# imsensor-esp-v01.net
KiCad netlist of a schematic drawn in EAGLE
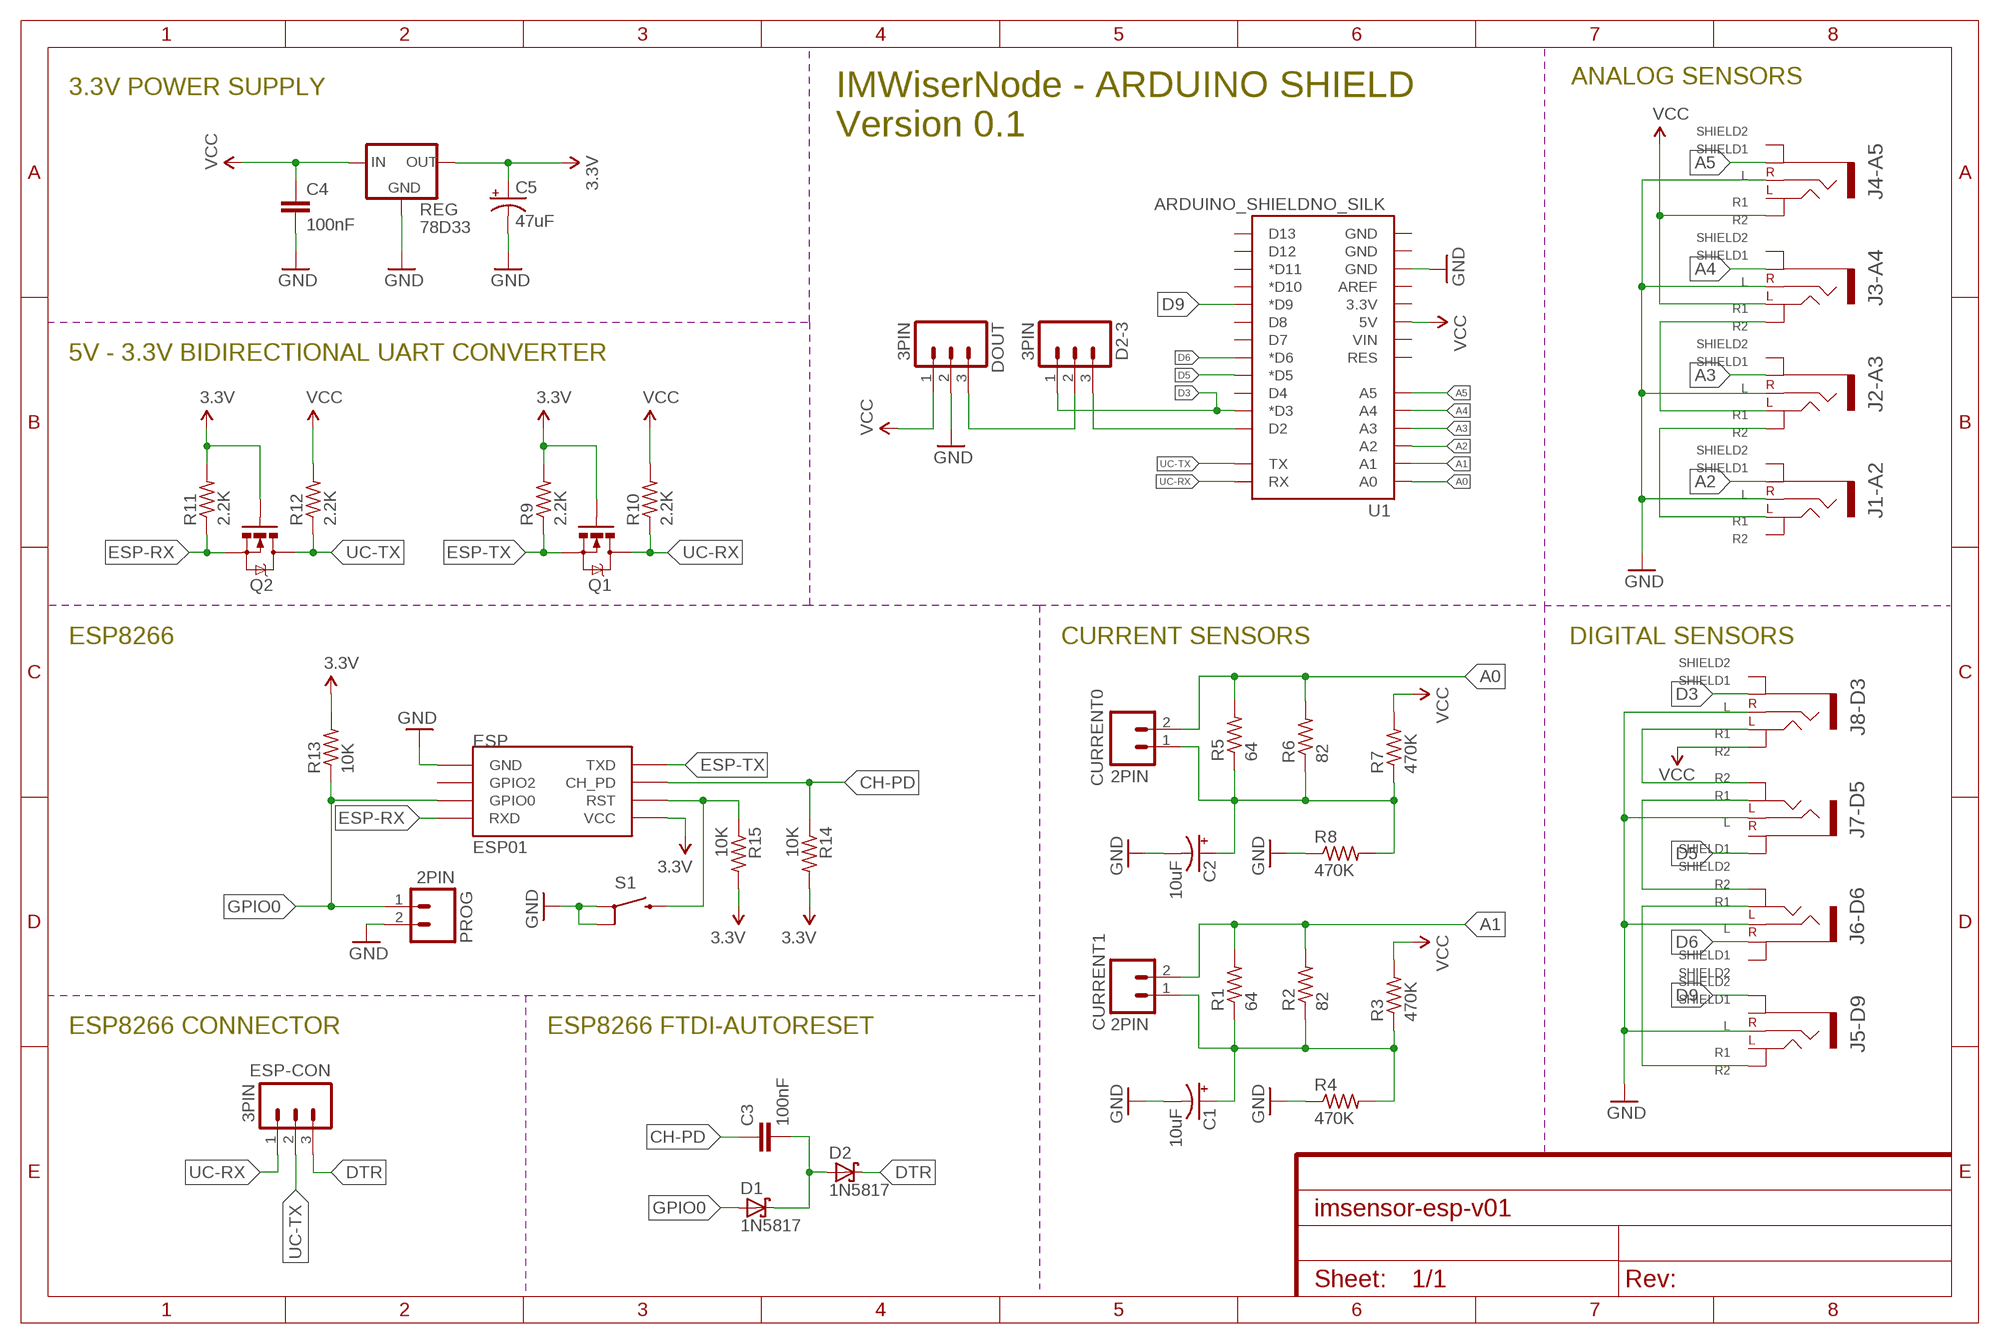
[diagram p0: schematic, sheet 1]

(export (version "E")
  (design (tool "Eeschema 10.0.6"))
  (components
    (comp (ref "C1")
      (value "10uF")
      (footprint "eagle-import:CPOL-RADIAL-10UF-25V")
      (libsource (lib "eagle-import") (part "10UF-25V-20%(PTH)"))
    )
    (comp (ref "C2")
      (value "10uF")
      (footprint "eagle-import:CPOL-RADIAL-10UF-25V")
      (libsource (lib "eagle-import") (part "10UF-25V-20%(PTH)"))
    )
    (comp (ref "C3")
      (value "100nF")
      (footprint "eagle-import:CAP-PTH-SMALL")
      (libsource (lib "eagle-import") (part "CAPPTH"))
    )
    (comp (ref "C4")
      (value "100nF")
      (footprint "eagle-import:CAP-PTH-SMALL")
      (libsource (lib "eagle-import") (part "CAPPTH"))
    )
    (comp (ref "C5")
      (value "47uF")
      (footprint "eagle-import:CPOL-RADIAL-10UF-25V")
      (libsource (lib "eagle-import") (part "10UF-25V-20%(PTH)"))
    )
    (comp (ref "CURRENT0")
      (value "2PIN")
      (footprint "eagle-import:1X02")
      (libsource (lib "eagle-import") (part "M02PTH"))
    )
    (comp (ref "CURRENT1")
      (value "2PIN")
      (footprint "eagle-import:1X02")
      (libsource (lib "eagle-import") (part "M02PTH"))
    )
    (comp (ref "D1")
      (value "1N5817")
      (footprint "eagle-import:DO41-7")
      (libsource (lib "eagle-import") (part "SCHOTTKY-DIODEDO41-7"))
    )
    (comp (ref "D2")
      (value "1N5817")
      (footprint "eagle-import:DO41-7")
      (libsource (lib "eagle-import") (part "SCHOTTKY-DIODEDO41-7"))
    )
    (comp (ref "D2-3")
      (value "3PIN")
      (footprint "eagle-import:1X03")
      (libsource (lib "eagle-import") (part "M03PTH"))
    )
    (comp (ref "DOUT")
      (value "3PIN")
      (footprint "eagle-import:1X03")
      (libsource (lib "eagle-import") (part "M03PTH"))
    )
    (comp (ref "ESP")
      (value "ESP01")
      (footprint "eagle-import:ESP01")
      (libsource (lib "eagle-import") (part "ESP01"))
    )
    (comp (ref "ESP-CON")
      (value "3PIN")
      (footprint "eagle-import:1X03")
      (libsource (lib "eagle-import") (part "M03PTH"))
    )
    (comp (ref "J1-A2")
      (value "PJ-313-SPAD")
      (footprint "eagle-import:PJ-313-5PIN-SMALL")
      (libsource (lib "eagle-import") (part "PJ-313-SPAD"))
    )
    (comp (ref "J2-A3")
      (value "PJ-313-SPAD")
      (footprint "eagle-import:PJ-313-5PIN-SMALL")
      (libsource (lib "eagle-import") (part "PJ-313-SPAD"))
    )
    (comp (ref "J3-A4")
      (value "PJ-313-SPAD")
      (footprint "eagle-import:PJ-313-5PIN-SMALL")
      (libsource (lib "eagle-import") (part "PJ-313-SPAD"))
    )
    (comp (ref "J4-A5")
      (value "PJ-313-SPAD")
      (footprint "eagle-import:PJ-313-5PIN-SMALL")
      (libsource (lib "eagle-import") (part "PJ-313-SPAD"))
    )
    (comp (ref "J5-D9")
      (value "PJ-313-SPAD")
      (footprint "eagle-import:PJ-313-5PIN-SMALL")
      (libsource (lib "eagle-import") (part "PJ-313-SPAD"))
    )
    (comp (ref "J6-D6")
      (value "PJ-313-SPAD")
      (footprint "eagle-import:PJ-313-5PIN-SMALL")
      (libsource (lib "eagle-import") (part "PJ-313-SPAD"))
    )
    (comp (ref "J7-D5")
      (value "PJ-313-SPAD")
      (footprint "eagle-import:PJ-313-5PIN-SMALL")
      (libsource (lib "eagle-import") (part "PJ-313-SPAD"))
    )
    (comp (ref "J8-D3")
      (value "PJ-313-SPAD")
      (footprint "eagle-import:PJ-313-5PIN-SMALL")
      (libsource (lib "eagle-import") (part "PJ-313-SPAD"))
    )
    (comp (ref "PROG")
      (value "2PIN")
      (footprint "eagle-import:1X02")
      (libsource (lib "eagle-import") (part "M02PTH"))
    )
    (comp (ref "Q1")
      (value "MOSFET-NCHANNEL2N7000")
      (footprint "eagle-import:TO-92")
      (libsource (lib "eagle-import") (part "MOSFET-NCHANNEL2N7000"))
    )
    (comp (ref "Q2")
      (value "MOSFET-NCHANNEL2N7000")
      (footprint "eagle-import:TO-92")
      (libsource (lib "eagle-import") (part "MOSFET-NCHANNEL2N7000"))
    )
    (comp (ref "R1")
      (value "64")
      (footprint "eagle-import:0207_10")
      (libsource (lib "eagle-import") (part "R-US_0207/10"))
    )
    (comp (ref "R2")
      (value "82")
      (footprint "eagle-import:0207_10")
      (libsource (lib "eagle-import") (part "R-US_0207/10"))
    )
    (comp (ref "R3")
      (value "470K")
      (footprint "eagle-import:0207_10")
      (libsource (lib "eagle-import") (part "R-US_0207/10"))
    )
    (comp (ref "R4")
      (value "470K")
      (footprint "eagle-import:0207_10")
      (libsource (lib "eagle-import") (part "R-US_0207/10"))
    )
    (comp (ref "R5")
      (value "64")
      (footprint "eagle-import:0207_10")
      (libsource (lib "eagle-import") (part "R-US_0207/10"))
    )
    (comp (ref "R6")
      (value "82")
      (footprint "eagle-import:0207_10")
      (libsource (lib "eagle-import") (part "R-US_0207/10"))
    )
    (comp (ref "R7")
      (value "470K")
      (footprint "eagle-import:0207_10")
      (libsource (lib "eagle-import") (part "R-US_0207/10"))
    )
    (comp (ref "R8")
      (value "470K")
      (footprint "eagle-import:0207_10")
      (libsource (lib "eagle-import") (part "R-US_0207/10"))
    )
    (comp (ref "R9")
      (value "2.2K")
      (footprint "eagle-import:0207_10")
      (libsource (lib "eagle-import") (part "R-US_0207/10"))
    )
    (comp (ref "R10")
      (value "2.2K")
      (footprint "eagle-import:0207_10")
      (libsource (lib "eagle-import") (part "R-US_0207/10"))
    )
    (comp (ref "R11")
      (value "2.2K")
      (footprint "eagle-import:0207_10")
      (libsource (lib "eagle-import") (part "R-US_0207/10"))
    )
    (comp (ref "R12")
      (value "2.2K")
      (footprint "eagle-import:0207_10")
      (libsource (lib "eagle-import") (part "R-US_0207/10"))
    )
    (comp (ref "R13")
      (value "10K")
      (footprint "eagle-import:0207_10")
      (libsource (lib "eagle-import") (part "R-US_0207/10"))
    )
    (comp (ref "R14")
      (value "10K")
      (footprint "eagle-import:0207_10")
      (libsource (lib "eagle-import") (part "R-US_0207/10"))
    )
    (comp (ref "R15")
      (value "10K")
      (footprint "eagle-import:0207_10")
      (libsource (lib "eagle-import") (part "R-US_0207/10"))
    )
    (comp (ref "REG")
      (value "78D33")
      (footprint "eagle-import:TO220-IGO")
      (libsource (lib "eagle-import") (part "V_REG_78XXSINK"))
    )
    (comp (ref "S1")
      (value "SWITCH-MOMENTARY-2PTH")
      (footprint "eagle-import:TACTILE-PTH")
      (libsource (lib "eagle-import") (part "SWITCH-MOMENTARY-2PTH"))
    )
    (comp (ref "U1")
      (value "ARDUINO_SHIELDNO_SILK")
      (footprint "eagle-import:DUEMILANOVE_VIAS")
      (libsource (lib "eagle-import") (part "ARDUINO_SHIELDNO_SILK"))
    )
  )
  (nets
    (net (code "1") (name "3.3V") (class "Default")
      (node (ref "C5") (pin "1") (pinfunction "+_1") (pintype "passive"))
      (node (ref "ESP") (pin "VCC") (pinfunction "VCC_VCC") (pintype "bidirectional"))
      (node (ref "Q1") (pin "2") (pinfunction "G_2") (pintype "passive"))
      (node (ref "Q2") (pin "2") (pinfunction "G_2") (pintype "passive"))
      (node (ref "R11") (pin "2") (pinfunction "2_2") (pintype "passive"))
      (node (ref "R13") (pin "2") (pinfunction "2_2") (pintype "passive"))
      (node (ref "R14") (pin "2") (pinfunction "2_2") (pintype "passive"))
      (node (ref "R15") (pin "2") (pinfunction "2_2") (pintype "passive"))
      (node (ref "R9") (pin "2") (pinfunction "2_2") (pintype "passive"))
      (node (ref "REG") (pin "OUT") (pinfunction "OUT_OUT") (pintype "passive"))
    )
    (net (code "2") (name "A0") (class "Default")
      (node (ref "CURRENT0") (pin "2") (pinfunction "2_2") (pintype "passive"))
      (node (ref "R5") (pin "2") (pinfunction "2_2") (pintype "passive"))
      (node (ref "R6") (pin "2") (pinfunction "2_2") (pintype "passive"))
      (node (ref "U1") (pin "A0") (pinfunction "A0_A0") (pintype "bidirectional"))
    )
    (net (code "3") (name "A1") (class "Default")
      (node (ref "CURRENT1") (pin "2") (pinfunction "2_2") (pintype "passive"))
      (node (ref "R1") (pin "2") (pinfunction "2_2") (pintype "passive"))
      (node (ref "R2") (pin "2") (pinfunction "2_2") (pintype "passive"))
      (node (ref "U1") (pin "A1") (pinfunction "A1_A1") (pintype "bidirectional"))
    )
    (net (code "4") (name "A2") (class "Default")
      (node (ref "J1-A2") (pin "1.1") (pinfunction "SHIELD1_1.1") (pintype "bidirectional"))
      (node (ref "U1") (pin "A2") (pinfunction "A2_A2") (pintype "bidirectional"))
    )
    (net (code "5") (name "A3") (class "Default")
      (node (ref "J2-A3") (pin "1.1") (pinfunction "SHIELD1_1.1") (pintype "bidirectional"))
      (node (ref "U1") (pin "A3") (pinfunction "A3_A3") (pintype "bidirectional"))
    )
    (net (code "6") (name "A4") (class "Default")
      (node (ref "J3-A4") (pin "1.1") (pinfunction "SHIELD1_1.1") (pintype "bidirectional"))
      (node (ref "U1") (pin "A4") (pinfunction "A4_A4") (pintype "bidirectional"))
    )
    (net (code "7") (name "A5") (class "Default")
      (node (ref "J4-A5") (pin "1.1") (pinfunction "SHIELD1_1.1") (pintype "bidirectional"))
      (node (ref "U1") (pin "A5") (pinfunction "A5_A5") (pintype "bidirectional"))
    )
    (net (code "8") (name "CH-PD") (class "Default")
      (node (ref "C3") (pin "1") (pinfunction "1_1") (pintype "passive"))
      (node (ref "ESP") (pin "CH_PD") (pinfunction "CH_PD_CH_PD") (pintype "bidirectional"))
      (node (ref "R14") (pin "1") (pinfunction "1_1") (pintype "passive"))
    )
    (net (code "9") (name "D3") (class "Default")
      (node (ref "D2-3") (pin "1") (pinfunction "1_1") (pintype "passive"))
      (node (ref "J8-D3") (pin "1.1") (pinfunction "SHIELD1_1.1") (pintype "bidirectional"))
      (node (ref "U1") (pin "D3") (pinfunction "*D3_D3") (pintype "bidirectional"))
    )
    (net (code "10") (name "D5") (class "Default")
      (node (ref "J7-D5") (pin "1.2") (pinfunction "SHIELD2_1.2") (pintype "bidirectional"))
      (node (ref "U1") (pin "D5") (pinfunction "*D5_D5") (pintype "bidirectional"))
    )
    (net (code "11") (name "D6") (class "Default")
      (node (ref "J6-D6") (pin "1.1") (pinfunction "SHIELD1_1.1") (pintype "bidirectional"))
      (node (ref "U1") (pin "D6") (pinfunction "*D6_D6") (pintype "bidirectional"))
    )
    (net (code "12") (name "D9") (class "Default")
      (node (ref "J5-D9") (pin "1.2") (pinfunction "SHIELD2_1.2") (pintype "bidirectional"))
      (node (ref "U1") (pin "D9") (pinfunction "*D9_D9") (pintype "bidirectional"))
    )
    (net (code "13") (name "DTR") (class "Default")
      (node (ref "D2") (pin "C") (pinfunction "C_C") (pintype "passive"))
      (node (ref "ESP-CON") (pin "3") (pinfunction "3_3") (pintype "passive"))
    )
    (net (code "14") (name "ESP-RX") (class "Default")
      (node (ref "ESP") (pin "RX") (pinfunction "RXD_RX") (pintype "bidirectional"))
      (node (ref "Q2") (pin "1") (pinfunction "S_1") (pintype "passive"))
      (node (ref "R11") (pin "1") (pinfunction "1_1") (pintype "passive"))
    )
    (net (code "15") (name "ESP-TX") (class "Default")
      (node (ref "ESP") (pin "TX") (pinfunction "TXD_TX") (pintype "bidirectional"))
      (node (ref "Q1") (pin "1") (pinfunction "S_1") (pintype "passive"))
      (node (ref "R9") (pin "1") (pinfunction "1_1") (pintype "passive"))
    )
    (net (code "16") (name "GND") (class "Default")
      (node (ref "C1") (pin "2") (pinfunction "-_2") (pintype "passive"))
      (node (ref "C2") (pin "2") (pinfunction "-_2") (pintype "passive"))
      (node (ref "C4") (pin "2") (pinfunction "2_2") (pintype "passive"))
      (node (ref "C5") (pin "2") (pinfunction "-_2") (pintype "passive"))
      (node (ref "DOUT") (pin "2") (pinfunction "2_2") (pintype "passive"))
      (node (ref "ESP") (pin "GND") (pinfunction "GND_GND") (pintype "bidirectional"))
      (node (ref "J1-A2") (pin "2") (pinfunction "R_2") (pintype "bidirectional"))
      (node (ref "J2-A3") (pin "2") (pinfunction "R_2") (pintype "bidirectional"))
      (node (ref "J3-A4") (pin "2") (pinfunction "R_2") (pintype "bidirectional"))
      (node (ref "J4-A5") (pin "2") (pinfunction "R_2") (pintype "bidirectional"))
      (node (ref "J5-D9") (pin "2") (pinfunction "R_2") (pintype "bidirectional"))
      (node (ref "J6-D6") (pin "2") (pinfunction "R_2") (pintype "bidirectional"))
      (node (ref "J7-D5") (pin "2") (pinfunction "R_2") (pintype "bidirectional"))
      (node (ref "J8-D3") (pin "2") (pinfunction "R_2") (pintype "bidirectional"))
      (node (ref "PROG") (pin "2") (pinfunction "2_2") (pintype "passive"))
      (node (ref "R4") (pin "1") (pinfunction "1_1") (pintype "passive"))
      (node (ref "R8") (pin "1") (pinfunction "1_1") (pintype "passive"))
      (node (ref "REG") (pin "GND") (pinfunction "GND_GND") (pintype "input"))
      (node (ref "S1") (pin "1") (pinfunction "1_1") (pintype "passive"))
      (node (ref "S1") (pin "2") (pinfunction "P$1_2") (pintype "passive"))
      (node (ref "U1") (pin "GND@2") (pinfunction "GND_GND@2") (pintype "bidirectional"))
    )
    (net (code "17") (name "GPIO0") (class "Default")
      (node (ref "D1") (pin "A") (pinfunction "A_A") (pintype "passive"))
      (node (ref "ESP") (pin "GPIO0") (pinfunction "GPIO0_GPIO0") (pintype "bidirectional"))
      (node (ref "PROG") (pin "1") (pinfunction "1_1") (pintype "passive"))
      (node (ref "R13") (pin "1") (pinfunction "1_1") (pintype "passive"))
    )
    (net (code "18") (name "Net-(C1-+)") (class "Default")
      (node (ref "C1") (pin "1") (pinfunction "+_1") (pintype "passive"))
      (node (ref "CURRENT1") (pin "1") (pinfunction "1_1") (pintype "passive"))
      (node (ref "R1") (pin "1") (pinfunction "1_1") (pintype "passive"))
      (node (ref "R2") (pin "1") (pinfunction "1_1") (pintype "passive"))
      (node (ref "R3") (pin "1") (pinfunction "1_1") (pintype "passive"))
      (node (ref "R4") (pin "2") (pinfunction "2_2") (pintype "passive"))
    )
    (net (code "19") (name "Net-(C2-+)") (class "Default")
      (node (ref "C2") (pin "1") (pinfunction "+_1") (pintype "passive"))
      (node (ref "CURRENT0") (pin "1") (pinfunction "1_1") (pintype "passive"))
      (node (ref "R5") (pin "1") (pinfunction "1_1") (pintype "passive"))
      (node (ref "R6") (pin "1") (pinfunction "1_1") (pintype "passive"))
      (node (ref "R7") (pin "1") (pinfunction "1_1") (pintype "passive"))
      (node (ref "R8") (pin "2") (pinfunction "2_2") (pintype "passive"))
    )
    (net (code "20") (name "Net-(C3-Pad2)") (class "Default")
      (node (ref "C3") (pin "2") (pinfunction "2_2") (pintype "passive"))
      (node (ref "D1") (pin "C") (pinfunction "C_C") (pintype "passive"))
      (node (ref "D2") (pin "A") (pinfunction "A_A") (pintype "passive"))
    )
    (net (code "21") (name "Net-(D2-3-Pad2)") (class "Default")
      (node (ref "D2-3") (pin "2") (pinfunction "2_2") (pintype "passive"))
      (node (ref "DOUT") (pin "3") (pinfunction "3_3") (pintype "passive"))
    )
    (net (code "22") (name "Net-(D2-3-Pad3)") (class "Default")
      (node (ref "D2-3") (pin "3") (pinfunction "3_3") (pintype "passive"))
      (node (ref "U1") (pin "D2") (pinfunction "D2_D2") (pintype "bidirectional"))
    )
    (net (code "23") (name "Net-(J1-A2-L1)") (class "Default")
      (node (ref "J1-A2") (pin "3.1") (pinfunction "L1_3.1") (pintype "bidirectional"))
      (node (ref "J2-A3") (pin "3.2") (pinfunction "L2_3.2") (pintype "bidirectional"))
    )
    (net (code "24") (name "Net-(J2-A3-L1)") (class "Default")
      (node (ref "J2-A3") (pin "3.1") (pinfunction "L1_3.1") (pintype "bidirectional"))
      (node (ref "J3-A4") (pin "3.2") (pinfunction "L2_3.2") (pintype "bidirectional"))
    )
    (net (code "25") (name "Net-(J5-D9-L2)") (class "Default")
      (node (ref "J5-D9") (pin "3.2") (pinfunction "L2_3.2") (pintype "bidirectional"))
      (node (ref "J6-D6") (pin "3.1") (pinfunction "L1_3.1") (pintype "bidirectional"))
    )
    (net (code "26") (name "Net-(J6-D6-L2)") (class "Default")
      (node (ref "J6-D6") (pin "3.2") (pinfunction "L2_3.2") (pintype "bidirectional"))
      (node (ref "J7-D5") (pin "3.1") (pinfunction "L1_3.1") (pintype "bidirectional"))
    )
    (net (code "27") (name "Net-(J7-D5-L2)") (class "Default")
      (node (ref "J7-D5") (pin "3.2") (pinfunction "L2_3.2") (pintype "bidirectional"))
      (node (ref "J8-D3") (pin "3.1") (pinfunction "L1_3.1") (pintype "bidirectional"))
    )
    (net (code "28") (name "Net-(S1-2)") (class "Default")
      (node (ref "ESP") (pin "RST") (pinfunction "RST_RST") (pintype "bidirectional"))
      (node (ref "R15") (pin "1") (pinfunction "1_1") (pintype "passive"))
      (node (ref "S1") (pin "3") (pinfunction "2_3") (pintype "passive"))
    )
    (net (code "29") (name "UC-RX") (class "Default")
      (node (ref "ESP-CON") (pin "1") (pinfunction "1_1") (pintype "passive"))
      (node (ref "Q1") (pin "3") (pinfunction "D_3") (pintype "passive"))
      (node (ref "R10") (pin "1") (pinfunction "1_1") (pintype "passive"))
      (node (ref "U1") (pin "RX") (pinfunction "RX_RX") (pintype "bidirectional"))
    )
    (net (code "30") (name "UC-TX") (class "Default")
      (node (ref "ESP-CON") (pin "2") (pinfunction "2_2") (pintype "passive"))
      (node (ref "Q2") (pin "3") (pinfunction "D_3") (pintype "passive"))
      (node (ref "R12") (pin "1") (pinfunction "1_1") (pintype "passive"))
      (node (ref "U1") (pin "TX") (pinfunction "TX_TX") (pintype "bidirectional"))
    )
    (net (code "31") (name "VCC") (class "Default")
      (node (ref "C4") (pin "1") (pinfunction "1_1") (pintype "passive"))
      (node (ref "DOUT") (pin "1") (pinfunction "1_1") (pintype "passive"))
      (node (ref "J3-A4") (pin "3.1") (pinfunction "L1_3.1") (pintype "bidirectional"))
      (node (ref "J4-A5") (pin "3.2") (pinfunction "L2_3.2") (pintype "bidirectional"))
      (node (ref "J8-D3") (pin "3.2") (pinfunction "L2_3.2") (pintype "bidirectional"))
      (node (ref "R10") (pin "2") (pinfunction "2_2") (pintype "passive"))
      (node (ref "R12") (pin "2") (pinfunction "2_2") (pintype "passive"))
      (node (ref "R3") (pin "2") (pinfunction "2_2") (pintype "passive"))
      (node (ref "R7") (pin "2") (pinfunction "2_2") (pintype "passive"))
      (node (ref "REG") (pin "IN") (pinfunction "IN_IN") (pintype "input"))
      (node (ref "U1") (pin "5V") (pinfunction "5V_5V") (pintype "bidirectional"))
    )
    (net (code "32") (name "unconnected-(ESP-PadGPIO2)") (class "Default")
      (node (ref "ESP") (pin "GPIO2") (pinfunction "GPIO2_GPIO2") (pintype "bidirectional"))
    )
    (net (code "33") (name "unconnected-(J1-A2-L2-Pad3.2)") (class "Default")
      (node (ref "J1-A2") (pin "3.2") (pinfunction "L2_3.2") (pintype "bidirectional"))
    )
    (net (code "34") (name "unconnected-(J1-A2-SHIELD2-Pad1.2)") (class "Default")
      (node (ref "J1-A2") (pin "1.2") (pinfunction "SHIELD2_1.2") (pintype "bidirectional"))
    )
    (net (code "35") (name "unconnected-(J2-A3-SHIELD2-Pad1.2)") (class "Default")
      (node (ref "J2-A3") (pin "1.2") (pinfunction "SHIELD2_1.2") (pintype "bidirectional"))
    )
    (net (code "36") (name "unconnected-(J3-A4-SHIELD2-Pad1.2)") (class "Default")
      (node (ref "J3-A4") (pin "1.2") (pinfunction "SHIELD2_1.2") (pintype "bidirectional"))
    )
    (net (code "37") (name "unconnected-(J4-A5-L1-Pad3.1)") (class "Default")
      (node (ref "J4-A5") (pin "3.1") (pinfunction "L1_3.1") (pintype "bidirectional"))
    )
    (net (code "38") (name "unconnected-(J4-A5-SHIELD2-Pad1.2)") (class "Default")
      (node (ref "J4-A5") (pin "1.2") (pinfunction "SHIELD2_1.2") (pintype "bidirectional"))
    )
    (net (code "39") (name "unconnected-(J5-D9-L1-Pad3.1)") (class "Default")
      (node (ref "J5-D9") (pin "3.1") (pinfunction "L1_3.1") (pintype "bidirectional"))
    )
    (net (code "40") (name "unconnected-(J5-D9-SHIELD1-Pad1.1)") (class "Default")
      (node (ref "J5-D9") (pin "1.1") (pinfunction "SHIELD1_1.1") (pintype "bidirectional"))
    )
    (net (code "41") (name "unconnected-(J6-D6-SHIELD2-Pad1.2)") (class "Default")
      (node (ref "J6-D6") (pin "1.2") (pinfunction "SHIELD2_1.2") (pintype "bidirectional"))
    )
    (net (code "42") (name "unconnected-(J7-D5-SHIELD1-Pad1.1)") (class "Default")
      (node (ref "J7-D5") (pin "1.1") (pinfunction "SHIELD1_1.1") (pintype "bidirectional"))
    )
    (net (code "43") (name "unconnected-(J8-D3-SHIELD2-Pad1.2)") (class "Default")
      (node (ref "J8-D3") (pin "1.2") (pinfunction "SHIELD2_1.2") (pintype "bidirectional"))
    )
    (net (code "44") (name "unconnected-(U1-*D10-PadD10)") (class "Default")
      (node (ref "U1") (pin "D10") (pinfunction "*D10_D10") (pintype "bidirectional"))
    )
    (net (code "45") (name "unconnected-(U1-*D11-PadD11)") (class "Default")
      (node (ref "U1") (pin "D11") (pinfunction "*D11_D11") (pintype "bidirectional"))
    )
    (net (code "46") (name "unconnected-(U1-GND-PadGND@0)") (class "Default")
      (node (ref "U1") (pin "GND@0") (pinfunction "GND_GND@0") (pintype "bidirectional"))
    )
    (net (code "47") (name "unconnected-(U1-GND-PadGND@1)") (class "Default")
      (node (ref "U1") (pin "GND@1") (pinfunction "GND_GND@1") (pintype "bidirectional"))
    )
    (net (code "48") (name "unconnected-(U1-Pad3.3V)") (class "Default")
      (node (ref "U1") (pin "3.3V") (pinfunction "3.3V_3.3V") (pintype "bidirectional"))
    )
    (net (code "49") (name "unconnected-(U1-PadAREF)") (class "Default")
      (node (ref "U1") (pin "AREF") (pinfunction "AREF_AREF") (pintype "bidirectional"))
    )
    (net (code "50") (name "unconnected-(U1-PadD4)") (class "Default")
      (node (ref "U1") (pin "D4") (pinfunction "D4_D4") (pintype "bidirectional"))
    )
    (net (code "51") (name "unconnected-(U1-PadD7)") (class "Default")
      (node (ref "U1") (pin "D7") (pinfunction "D7_D7") (pintype "bidirectional"))
    )
    (net (code "52") (name "unconnected-(U1-PadD8)") (class "Default")
      (node (ref "U1") (pin "D8") (pinfunction "D8_D8") (pintype "bidirectional"))
    )
    (net (code "53") (name "unconnected-(U1-PadD12)") (class "Default")
      (node (ref "U1") (pin "D12") (pinfunction "D12_D12") (pintype "bidirectional"))
    )
    (net (code "54") (name "unconnected-(U1-PadD13)") (class "Default")
      (node (ref "U1") (pin "D13") (pinfunction "D13_D13") (pintype "bidirectional"))
    )
    (net (code "55") (name "unconnected-(U1-PadRES)") (class "Default")
      (node (ref "U1") (pin "RES") (pinfunction "RES_RES") (pintype "bidirectional"))
    )
    (net (code "56") (name "unconnected-(U1-PadVIN)") (class "Default")
      (node (ref "U1") (pin "VIN") (pinfunction "VIN_VIN") (pintype "bidirectional"))
    )
  )
)
